# tubitak.net
KiCad netlist of a schematic drawn in EAGLE
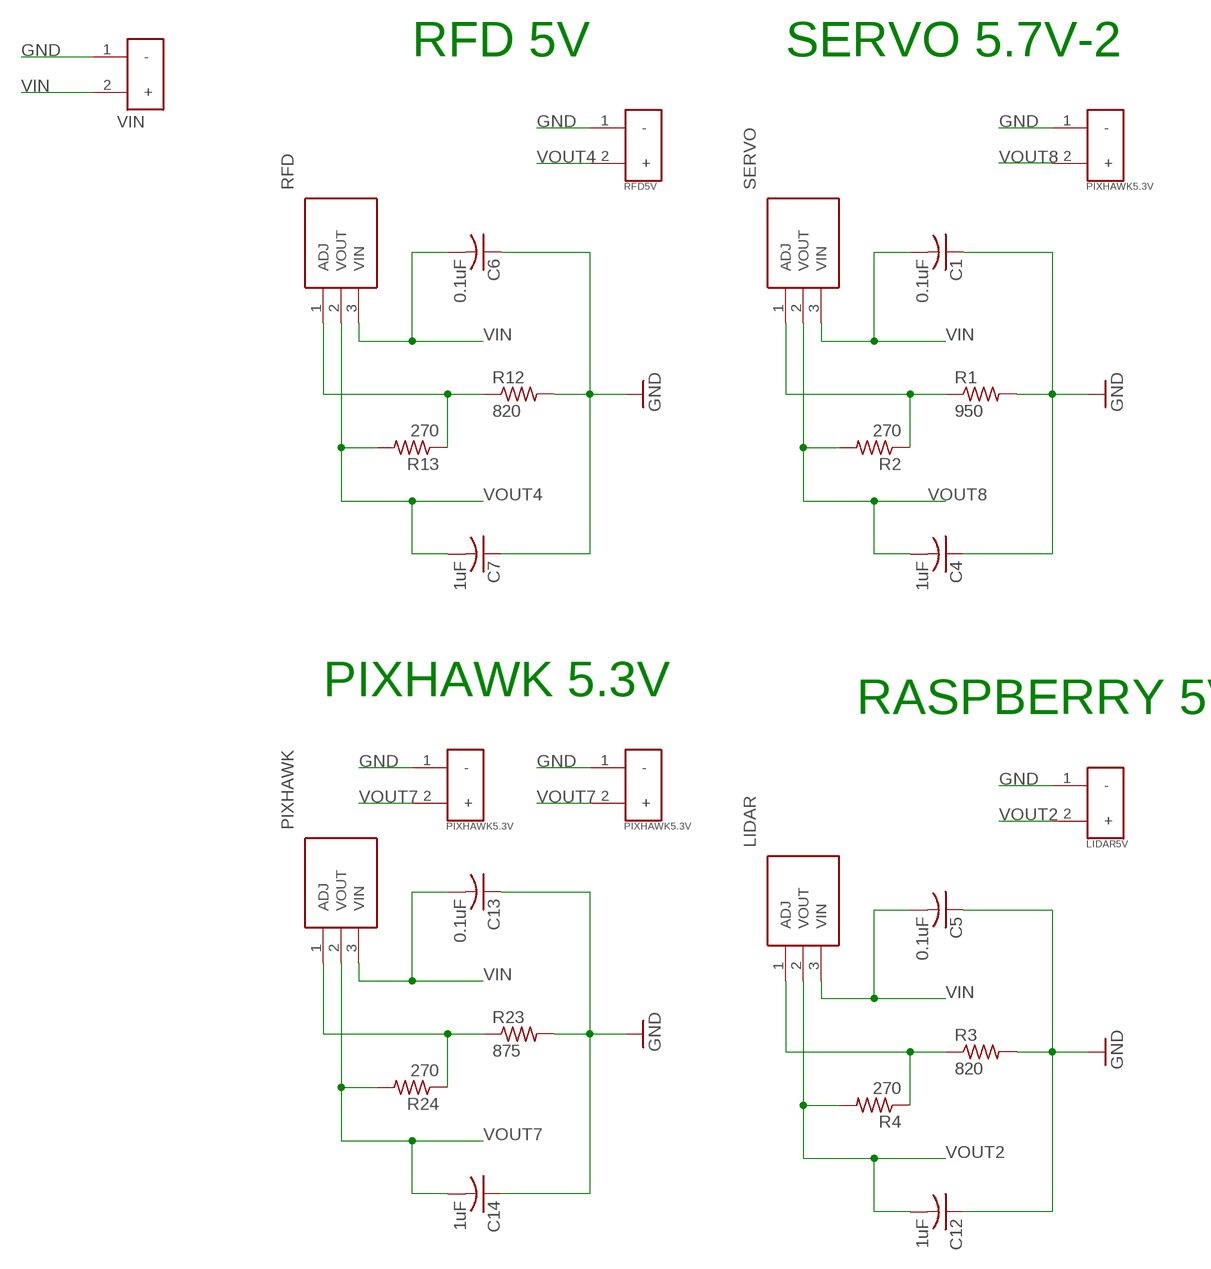
[diagram p0: schematic, sheet 1]

(export (version "E")
  (design (tool "Eeschema 10.0.6"))
  (components
    (comp (ref "C1")
      (value "0.1uF")
      (footprint "eagle-import:C0402K")
      (libsource (lib "eagle-import") (part "C-USC0402K"))
    )
    (comp (ref "C4")
      (value "1uF")
      (footprint "eagle-import:C0402K")
      (libsource (lib "eagle-import") (part "C-USC0402K"))
    )
    (comp (ref "C5")
      (value "0.1uF")
      (footprint "eagle-import:C0402K")
      (libsource (lib "eagle-import") (part "C-USC0402K"))
    )
    (comp (ref "C6")
      (value "0.1uF")
      (footprint "eagle-import:C0402K")
      (libsource (lib "eagle-import") (part "C-USC0402K"))
    )
    (comp (ref "C7")
      (value "1uF")
      (footprint "eagle-import:C0402K")
      (libsource (lib "eagle-import") (part "C-USC0402K"))
    )
    (comp (ref "C12")
      (value "1uF")
      (footprint "eagle-import:C0402K")
      (libsource (lib "eagle-import") (part "C-USC0402K"))
    )
    (comp (ref "C13")
      (value "0.1uF")
      (footprint "eagle-import:C0402K")
      (libsource (lib "eagle-import") (part "C-USC0402K"))
    )
    (comp (ref "C14")
      (value "1uF")
      (footprint "eagle-import:C0402K")
      (libsource (lib "eagle-import") (part "C-USC0402K"))
    )
    (comp (ref "J3")
      (value "VIN")
      (footprint "eagle-import:AMASS_XT60-M")
      (fields (field (name "MF") "AMASS") (field (name "MP") "XT60-M"))
      (libsource (lib "eagle-import") (part "XT60-M"))
    )
    (comp (ref "PIXHAWK")
      (value "PIXHAWK")
      (footprint "eagle-import:TO254P470X1028X1955-3P")
      (fields
        (field (name "ARROW_PART_NUMBER") "LM338T/NOPB")
        (field (name "MOUSER_PART_NUMBER") "926-LM338T/NOPB")
      )
      (libsource (lib "eagle-import") (part "LM338T_NOPB"))
    )
    (comp (ref "PIXHAWK5.3V-1")
      (value "PIXHAWK5.3V")
      (footprint "eagle-import:AMASS_XT60-M")
      (fields (field (name "MF") "AMASS") (field (name "MP") "XT60-M"))
      (libsource (lib "eagle-import") (part "XT60-M"))
    )
    (comp (ref "PIXHAWK5.3V-2")
      (value "PIXHAWK5.3V")
      (footprint "eagle-import:AMASS_XT60-M")
      (fields (field (name "MF") "AMASS") (field (name "MP") "XT60-M"))
      (libsource (lib "eagle-import") (part "XT60-M"))
    )
    (comp (ref "R1")
      (value "950")
      (footprint "eagle-import:R0805")
      (libsource (lib "eagle-import") (part "R-US_R0805"))
    )
    (comp (ref "R2")
      (value "270")
      (footprint "eagle-import:R0805")
      (libsource (lib "eagle-import") (part "R-US_R0805"))
    )
    (comp (ref "R3")
      (value "820")
      (footprint "eagle-import:R0805")
      (libsource (lib "eagle-import") (part "R-US_R0805"))
    )
    (comp (ref "R4")
      (value "270")
      (footprint "eagle-import:R0805")
      (libsource (lib "eagle-import") (part "R-US_R0805"))
    )
    (comp (ref "R12")
      (value "820")
      (footprint "eagle-import:R0805")
      (libsource (lib "eagle-import") (part "R-US_R0805"))
    )
    (comp (ref "R13")
      (value "270")
      (footprint "eagle-import:R0805")
      (libsource (lib "eagle-import") (part "R-US_R0805"))
    )
    (comp (ref "R23")
      (value "875")
      (footprint "eagle-import:R0805")
      (libsource (lib "eagle-import") (part "R-US_R0805"))
    )
    (comp (ref "R24")
      (value "270")
      (footprint "eagle-import:R0805")
      (libsource (lib "eagle-import") (part "R-US_R0805"))
    )
    (comp (ref "RASPBERRY")
      (value "LIDAR")
      (footprint "eagle-import:TO254P470X1028X1955-3P")
      (fields
        (field (name "ARROW_PART_NUMBER") "LM338T/NOPB")
        (field (name "MOUSER_PART_NUMBER") "926-LM338T/NOPB")
      )
      (libsource (lib "eagle-import") (part "LM338T_NOPB"))
    )
    (comp (ref "RASPBERRY5V")
      (value "LIDAR5V")
      (footprint "eagle-import:AMASS_XT60-M")
      (fields (field (name "MF") "AMASS") (field (name "MP") "XT60-M"))
      (libsource (lib "eagle-import") (part "XT60-M"))
    )
    (comp (ref "RFD")
      (value "RFD")
      (footprint "eagle-import:TO254P470X1028X1955-3P")
      (fields
        (field (name "ARROW_PART_NUMBER") "LM338T/NOPB")
        (field (name "MOUSER_PART_NUMBER") "926-LM338T/NOPB")
      )
      (libsource (lib "eagle-import") (part "LM338T_NOPB"))
    )
    (comp (ref "RFD5V")
      (value "RFD5V")
      (footprint "eagle-import:AMASS_XT60-M")
      (fields (field (name "MF") "AMASS") (field (name "MP") "XT60-M"))
      (libsource (lib "eagle-import") (part "XT60-M"))
    )
    (comp (ref "SERVO-2")
      (value "SERVO")
      (footprint "eagle-import:TO254P470X1028X1955-3P")
      (fields
        (field (name "ARROW_PART_NUMBER") "LM338T/NOPB")
        (field (name "MOUSER_PART_NUMBER") "926-LM338T/NOPB")
      )
      (libsource (lib "eagle-import") (part "LM338T_NOPB"))
    )
    (comp (ref "SERVO5.7V-2")
      (value "PIXHAWK5.3V")
      (footprint "eagle-import:AMASS_XT60-M")
      (fields (field (name "MF") "AMASS") (field (name "MP") "XT60-M"))
      (libsource (lib "eagle-import") (part "XT60-M"))
    )
  )
  (nets
    (net (code "1") (name "/VIN") (class "Default")
      (node (ref "C1") (pin "2") (pinfunction "2_2") (pintype "passive"))
      (node (ref "C13") (pin "2") (pinfunction "2_2") (pintype "passive"))
      (node (ref "C5") (pin "2") (pinfunction "2_2") (pintype "passive"))
      (node (ref "C6") (pin "2") (pinfunction "2_2") (pintype "passive"))
      (node (ref "J3") (pin "2") (pinfunction "+_2") (pintype "passive"))
      (node (ref "PIXHAWK") (pin "3") (pinfunction "VIN_3") (pintype "bidirectional"))
      (node (ref "RASPBERRY") (pin "3") (pinfunction "VIN_3") (pintype "bidirectional"))
      (node (ref "RFD") (pin "3") (pinfunction "VIN_3") (pintype "bidirectional"))
      (node (ref "SERVO-2") (pin "3") (pinfunction "VIN_3") (pintype "bidirectional"))
    )
    (net (code "2") (name "/VOUT2") (class "Default")
      (node (ref "C12") (pin "2") (pinfunction "2_2") (pintype "passive"))
      (node (ref "R4") (pin "2") (pinfunction "2_2") (pintype "passive"))
      (node (ref "RASPBERRY") (pin "2") (pinfunction "VOUT_2") (pintype "bidirectional"))
      (node (ref "RASPBERRY5V") (pin "2") (pinfunction "+_2") (pintype "passive"))
    )
    (net (code "3") (name "/VOUT4") (class "Default")
      (node (ref "C7") (pin "2") (pinfunction "2_2") (pintype "passive"))
      (node (ref "R13") (pin "2") (pinfunction "2_2") (pintype "passive"))
      (node (ref "RFD") (pin "2") (pinfunction "VOUT_2") (pintype "bidirectional"))
      (node (ref "RFD5V") (pin "2") (pinfunction "+_2") (pintype "passive"))
    )
    (net (code "4") (name "/VOUT7") (class "Default")
      (node (ref "C14") (pin "2") (pinfunction "2_2") (pintype "passive"))
      (node (ref "PIXHAWK") (pin "2") (pinfunction "VOUT_2") (pintype "bidirectional"))
      (node (ref "PIXHAWK5.3V-1") (pin "2") (pinfunction "+_2") (pintype "passive"))
      (node (ref "PIXHAWK5.3V-2") (pin "2") (pinfunction "+_2") (pintype "passive"))
      (node (ref "R24") (pin "2") (pinfunction "2_2") (pintype "passive"))
    )
    (net (code "5") (name "/VOUT8") (class "Default")
      (node (ref "C4") (pin "2") (pinfunction "2_2") (pintype "passive"))
      (node (ref "R2") (pin "2") (pinfunction "2_2") (pintype "passive"))
      (node (ref "SERVO-2") (pin "2") (pinfunction "VOUT_2") (pintype "bidirectional"))
      (node (ref "SERVO5.7V-2") (pin "2") (pinfunction "+_2") (pintype "passive"))
    )
    (net (code "6") (name "GND") (class "Default")
      (node (ref "C1") (pin "1") (pinfunction "1_1") (pintype "passive"))
      (node (ref "C12") (pin "1") (pinfunction "1_1") (pintype "passive"))
      (node (ref "C13") (pin "1") (pinfunction "1_1") (pintype "passive"))
      (node (ref "C14") (pin "1") (pinfunction "1_1") (pintype "passive"))
      (node (ref "C4") (pin "1") (pinfunction "1_1") (pintype "passive"))
      (node (ref "C5") (pin "1") (pinfunction "1_1") (pintype "passive"))
      (node (ref "C6") (pin "1") (pinfunction "1_1") (pintype "passive"))
      (node (ref "C7") (pin "1") (pinfunction "1_1") (pintype "passive"))
      (node (ref "J3") (pin "1") (pinfunction "-_1") (pintype "passive"))
      (node (ref "PIXHAWK5.3V-1") (pin "1") (pinfunction "-_1") (pintype "passive"))
      (node (ref "PIXHAWK5.3V-2") (pin "1") (pinfunction "-_1") (pintype "passive"))
      (node (ref "R1") (pin "2") (pinfunction "2_2") (pintype "passive"))
      (node (ref "R12") (pin "2") (pinfunction "2_2") (pintype "passive"))
      (node (ref "R23") (pin "2") (pinfunction "2_2") (pintype "passive"))
      (node (ref "R3") (pin "2") (pinfunction "2_2") (pintype "passive"))
      (node (ref "RASPBERRY5V") (pin "1") (pinfunction "-_1") (pintype "passive"))
      (node (ref "RFD5V") (pin "1") (pinfunction "-_1") (pintype "passive"))
      (node (ref "SERVO5.7V-2") (pin "1") (pinfunction "-_1") (pintype "passive"))
    )
    (net (code "7") (name "Net-(PIXHAWK-ADJ)") (class "Default")
      (node (ref "PIXHAWK") (pin "1") (pinfunction "ADJ_1") (pintype "bidirectional"))
      (node (ref "R23") (pin "1") (pinfunction "1_1") (pintype "passive"))
      (node (ref "R24") (pin "1") (pinfunction "1_1") (pintype "passive"))
    )
    (net (code "8") (name "Net-(RASPBERRY-ADJ)") (class "Default")
      (node (ref "R3") (pin "1") (pinfunction "1_1") (pintype "passive"))
      (node (ref "R4") (pin "1") (pinfunction "1_1") (pintype "passive"))
      (node (ref "RASPBERRY") (pin "1") (pinfunction "ADJ_1") (pintype "bidirectional"))
    )
    (net (code "9") (name "Net-(RFD-ADJ)") (class "Default")
      (node (ref "R12") (pin "1") (pinfunction "1_1") (pintype "passive"))
      (node (ref "R13") (pin "1") (pinfunction "1_1") (pintype "passive"))
      (node (ref "RFD") (pin "1") (pinfunction "ADJ_1") (pintype "bidirectional"))
    )
    (net (code "10") (name "Net-(SERVO-2-ADJ)") (class "Default")
      (node (ref "R1") (pin "1") (pinfunction "1_1") (pintype "passive"))
      (node (ref "R2") (pin "1") (pinfunction "1_1") (pintype "passive"))
      (node (ref "SERVO-2") (pin "1") (pinfunction "ADJ_1") (pintype "bidirectional"))
    )
  )
)
